# 1-Schematic_paystsn.net
KiCad netlist of a schematic drawn in EasyEDA
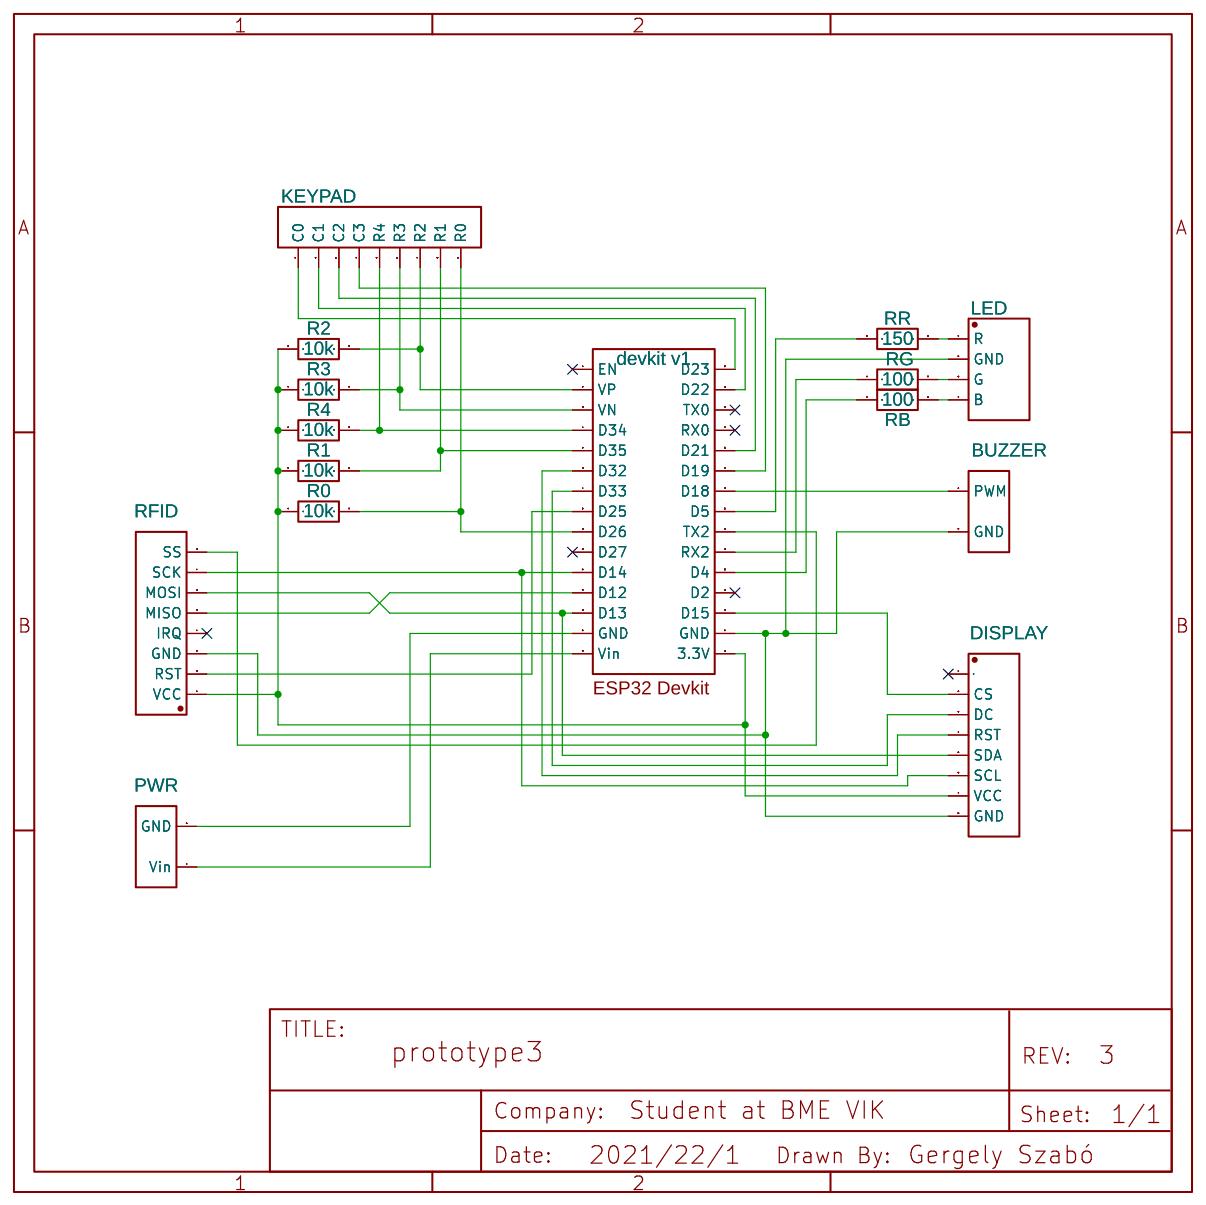
[diagram p0: schematic sheet]

(export (version "E")
  (design (tool "Eeschema 10.0.6"))
  (components
    (comp (ref "BUZZER")
      (value "Buzzer")
      (fields (field (name "BOM_Manufacturer Part") "826629-2") (field (name "BOM_Supplier Part") "C86471"))
      (libsource (lib "") (part "Header-Male-2.54_1x2_1"))
    )
    (comp (ref "DISPLAY")
      (value "Display")
      (fields
        (field (name "BOM_Manufacturer Part") "210S-1*8P L=11.6MMGold-plated black")
        (field (name "BOM_Supplier Part") "C124381")
      )
      (libsource (lib "") (part "Header-Male-2.54_1x8"))
    )
    (comp (ref "ESP32") (value "devkit v1") (libsource (lib "") (part "esp32")))
    (comp (ref "KEYPAD")
      (value "Keypad")
      (fields
        (field (name "BOM_Manufacturer Part") "2.54mm 1*9 Straight Female header")
        (field (name "BOM_Supplier Part") "C39576")
      )
      (libsource (lib "") (part "Header-Female-2.54_1x9"))
    )
    (comp (ref "LED")
      (value "LED")
      (fields
        (field (name "BOM_Manufacturer Part") "210S-1*4P L=11.6MMGold-plated black")
        (field (name "BOM_Supplier Part") "C124378")
      )
      (libsource (lib "") (part "Header-Male-2.54_1x4"))
    )
    (comp (ref "PWR")
      (value "Power")
      (fields (field (name "BOM_Manufacturer Part") "826629-2") (field (name "BOM_Supplier Part") "C86471"))
      (libsource (lib "") (part "Header-Male-2.54_1x2"))
    )
    (comp (ref "R0") (value "10k") (libsource (lib "") (part "R_0603_EU")))
    (comp (ref "R1") (value "10k") (libsource (lib "") (part "R_0603_EU")))
    (comp (ref "R2") (value "10k") (libsource (lib "") (part "R_0603_EU")))
    (comp (ref "R3") (value "10k") (libsource (lib "") (part "R_0603_EU")))
    (comp (ref "R4") (value "10k") (libsource (lib "") (part "R_0603_EU")))
    (comp (ref "RB") (value "100") (libsource (lib "") (part "R_0603_EU_3")))
    (comp (ref "RFID")
      (value "RFID")
      (fields
        (field (name "BOM_Manufacturer Part") "210S-1*8P L=11.6MMGold-plated black")
        (field (name "BOM_Supplier Part") "C124381")
      )
      (libsource (lib "") (part "Header-Male-2.54_1x8_1"))
    )
    (comp (ref "RG") (value "100") (libsource (lib "") (part "R_0603_EU_1")))
    (comp (ref "RR") (value "150") (libsource (lib "") (part "R_0603_EU_2")))
  )
  (nets
    (net (code "1") (name "Net-(BUZZER-GND)") (class "Default")
      (node (ref "BUZZER") (pin "2") (pinfunction "GND_2") (pintype "unspecified"))
      (node (ref "DISPLAY") (pin "8") (pinfunction "GND_8") (pintype "unspecified"))
      (node (ref "ESP32") (pin "17") (pinfunction "GND_17") (pintype "unspecified"))
      (node (ref "LED") (pin "2") (pinfunction "GND_2") (pintype "unspecified"))
      (node (ref "RFID") (pin "3") (pinfunction "GND_3") (pintype "unspecified"))
    )
    (net (code "2") (name "Net-(BUZZER-PWM)") (class "Default")
      (node (ref "BUZZER") (pin "1") (pinfunction "PWM_1") (pintype "unspecified"))
      (node (ref "ESP32") (pin "24") (pinfunction "D18_24") (pintype "unspecified"))
    )
    (net (code "3") (name "Net-(DISPLAY-CS)") (class "Default")
      (node (ref "DISPLAY") (pin "2") (pinfunction "CS_2") (pintype "unspecified"))
      (node (ref "ESP32") (pin "18") (pinfunction "D15_18") (pintype "unspecified"))
    )
    (net (code "4") (name "Net-(DISPLAY-DC)") (class "Default")
      (node (ref "DISPLAY") (pin "3") (pinfunction "DC_3") (pintype "unspecified"))
      (node (ref "ESP32") (pin "7") (pinfunction "D33_7") (pintype "unspecified"))
    )
    (net (code "5") (name "Net-(DISPLAY-RST)") (class "Default")
      (node (ref "DISPLAY") (pin "4") (pinfunction "RST_4") (pintype "unspecified"))
      (node (ref "ESP32") (pin "6") (pinfunction "D32_6") (pintype "unspecified"))
    )
    (net (code "6") (name "Net-(DISPLAY-SCL)") (class "Default")
      (node (ref "DISPLAY") (pin "6") (pinfunction "SCL_6") (pintype "unspecified"))
      (node (ref "ESP32") (pin "11") (pinfunction "D14_11") (pintype "unspecified"))
      (node (ref "RFID") (pin "7") (pinfunction "SCK_7") (pintype "unspecified"))
    )
    (net (code "7") (name "Net-(DISPLAY-SDA)") (class "Default")
      (node (ref "DISPLAY") (pin "5") (pinfunction "SDA_5") (pintype "unspecified"))
      (node (ref "ESP32") (pin "13") (pinfunction "D13_13") (pintype "unspecified"))
      (node (ref "RFID") (pin "6") (pinfunction "MOSI_6") (pintype "unspecified"))
    )
    (net (code "8") (name "Net-(DISPLAY-VCC)") (class "Default")
      (node (ref "DISPLAY") (pin "7") (pinfunction "VCC_7") (pintype "passive"))
      (node (ref "ESP32") (pin "16") (pinfunction "3.3V_16") (pintype "unspecified"))
      (node (ref "R0") (pin "1") (pinfunction "1_1") (pintype "unspecified"))
      (node (ref "R1") (pin "1") (pinfunction "1_1") (pintype "unspecified"))
      (node (ref "R2") (pin "1") (pinfunction "1_1") (pintype "unspecified"))
      (node (ref "R3") (pin "1") (pinfunction "1_1") (pintype "unspecified"))
      (node (ref "R4") (pin "1") (pinfunction "1_1") (pintype "unspecified"))
      (node (ref "RFID") (pin "1") (pinfunction "VCC_1") (pintype "unspecified"))
    )
    (net (code "9") (name "Net-(ESP32-D4)") (class "Default")
      (node (ref "ESP32") (pin "20") (pinfunction "D4_20") (pintype "unspecified"))
      (node (ref "RB") (pin "1") (pinfunction "1_1") (pintype "unspecified"))
    )
    (net (code "10") (name "Net-(ESP32-D5)") (class "Default")
      (node (ref "ESP32") (pin "23") (pinfunction "D5_23") (pintype "unspecified"))
      (node (ref "RR") (pin "1") (pinfunction "1_1") (pintype "unspecified"))
    )
    (net (code "11") (name "Net-(ESP32-D12)") (class "Default")
      (node (ref "ESP32") (pin "12") (pinfunction "D12_12") (pintype "unspecified"))
      (node (ref "RFID") (pin "5") (pinfunction "MISO_5") (pintype "unspecified"))
    )
    (net (code "12") (name "Net-(ESP32-D19)") (class "Default")
      (node (ref "ESP32") (pin "25") (pinfunction "D19_25") (pintype "unspecified"))
      (node (ref "KEYPAD") (pin "4") (pinfunction "C3_4") (pintype "input"))
    )
    (net (code "13") (name "Net-(ESP32-D21)") (class "Default")
      (node (ref "ESP32") (pin "26") (pinfunction "D21_26") (pintype "unspecified"))
      (node (ref "KEYPAD") (pin "3") (pinfunction "C2_3") (pintype "input"))
    )
    (net (code "14") (name "Net-(ESP32-D22)") (class "Default")
      (node (ref "ESP32") (pin "29") (pinfunction "D22_29") (pintype "unspecified"))
      (node (ref "KEYPAD") (pin "2") (pinfunction "C1_2") (pintype "input"))
    )
    (net (code "15") (name "Net-(ESP32-D23)") (class "Default")
      (node (ref "ESP32") (pin "30") (pinfunction "D23_30") (pintype "unspecified"))
      (node (ref "KEYPAD") (pin "1") (pinfunction "C0_1") (pintype "input"))
    )
    (net (code "16") (name "Net-(ESP32-D25)") (class "Default")
      (node (ref "ESP32") (pin "8") (pinfunction "D25_8") (pintype "unspecified"))
      (node (ref "RFID") (pin "2") (pinfunction "RST_2") (pintype "unspecified"))
    )
    (net (code "17") (name "Net-(ESP32-D26)") (class "Default")
      (node (ref "ESP32") (pin "9") (pinfunction "D26_9") (pintype "unspecified"))
      (node (ref "KEYPAD") (pin "9") (pinfunction "R0_9") (pintype "input"))
      (node (ref "R0") (pin "2") (pinfunction "2_2") (pintype "unspecified"))
    )
    (net (code "18") (name "Net-(ESP32-D34)") (class "Default")
      (node (ref "ESP32") (pin "4") (pinfunction "D34_4") (pintype "unspecified"))
      (node (ref "KEYPAD") (pin "5") (pinfunction "R4_5") (pintype "input"))
      (node (ref "R4") (pin "2") (pinfunction "2_2") (pintype "unspecified"))
    )
    (net (code "19") (name "Net-(ESP32-D35)") (class "Default")
      (node (ref "ESP32") (pin "5") (pinfunction "D35_5") (pintype "unspecified"))
      (node (ref "KEYPAD") (pin "8") (pinfunction "R1_8") (pintype "input"))
      (node (ref "R1") (pin "2") (pinfunction "2_2") (pintype "unspecified"))
    )
    (net (code "20") (name "Net-(ESP32-RX2)") (class "Default")
      (node (ref "ESP32") (pin "21") (pinfunction "RX2_21") (pintype "unspecified"))
      (node (ref "RG") (pin "1") (pinfunction "1_1") (pintype "unspecified"))
    )
    (net (code "21") (name "Net-(ESP32-TX2)") (class "Default")
      (node (ref "ESP32") (pin "22") (pinfunction "TX2_22") (pintype "unspecified"))
      (node (ref "RFID") (pin "8") (pinfunction "SS_8") (pintype "unspecified"))
    )
    (net (code "22") (name "Net-(ESP32-VN)") (class "Default")
      (node (ref "ESP32") (pin "3") (pinfunction "VN_3") (pintype "unspecified"))
      (node (ref "KEYPAD") (pin "6") (pinfunction "R3_6") (pintype "input"))
      (node (ref "R3") (pin "2") (pinfunction "2_2") (pintype "unspecified"))
    )
    (net (code "23") (name "Net-(ESP32-VP)") (class "Default")
      (node (ref "ESP32") (pin "2") (pinfunction "VP_2") (pintype "unspecified"))
      (node (ref "KEYPAD") (pin "7") (pinfunction "R2_7") (pintype "input"))
      (node (ref "R2") (pin "2") (pinfunction "2_2") (pintype "unspecified"))
    )
    (net (code "24") (name "Net-(ESP32-Vin)") (class "Default")
      (node (ref "ESP32") (pin "15") (pinfunction "Vin_15") (pintype "unspecified"))
      (node (ref "PWR") (pin "1") (pinfunction "Vin_1") (pintype "unspecified"))
    )
    (net (code "25") (name "Net-(LED-B)") (class "Default")
      (node (ref "LED") (pin "4") (pinfunction "B_4") (pintype "unspecified"))
      (node (ref "RB") (pin "2") (pinfunction "2_2") (pintype "unspecified"))
    )
    (net (code "26") (name "Net-(LED-G)") (class "Default")
      (node (ref "LED") (pin "3") (pinfunction "G_3") (pintype "unspecified"))
      (node (ref "RG") (pin "2") (pinfunction "2_2") (pintype "unspecified"))
    )
    (net (code "27") (name "Net-(LED-R)") (class "Default")
      (node (ref "LED") (pin "1") (pinfunction "R_1") (pintype "unspecified"))
      (node (ref "RR") (pin "2") (pinfunction "2_2") (pintype "unspecified"))
    )
    (net (code "28") (name "Net-(PWR-GND)") (class "Default")
      (node (ref "ESP32") (pin "14") (pinfunction "GND_14") (pintype "unspecified"))
      (node (ref "PWR") (pin "2") (pinfunction "GND_2") (pintype "unspecified"))
    )
    (net (code "29") (name "unconnected-(DISPLAY-Pad1)") (class "Default")
      (node (ref "DISPLAY") (pin "1") (pinfunction "1_1") (pintype "unspecified+no_connect"))
    )
    (net (code "30") (name "unconnected-(ESP32-D2-Pad19)") (class "Default")
      (node (ref "ESP32") (pin "19") (pinfunction "D2_19") (pintype "unspecified+no_connect"))
    )
    (net (code "31") (name "unconnected-(ESP32-D27-Pad10)") (class "Default")
      (node (ref "ESP32") (pin "10") (pinfunction "D27_10") (pintype "unspecified+no_connect"))
    )
    (net (code "32") (name "unconnected-(ESP32-EN-Pad1)") (class "Default")
      (node (ref "ESP32") (pin "1") (pinfunction "EN_1") (pintype "unspecified+no_connect"))
    )
    (net (code "33") (name "unconnected-(ESP32-RX0-Pad27)") (class "Default")
      (node (ref "ESP32") (pin "27") (pinfunction "RX0_27") (pintype "unspecified+no_connect"))
    )
    (net (code "34") (name "unconnected-(ESP32-TX0-Pad28)") (class "Default")
      (node (ref "ESP32") (pin "28") (pinfunction "TX0_28") (pintype "unspecified+no_connect"))
    )
    (net (code "35") (name "unconnected-(RFID-IRQ-Pad4)") (class "Default")
      (node (ref "RFID") (pin "4") (pinfunction "IRQ_4") (pintype "unspecified+no_connect"))
    )
  )
)
